# SH2_-_CONNECTORS.net
KiCad netlist of a schematic drawn in Altium Designer
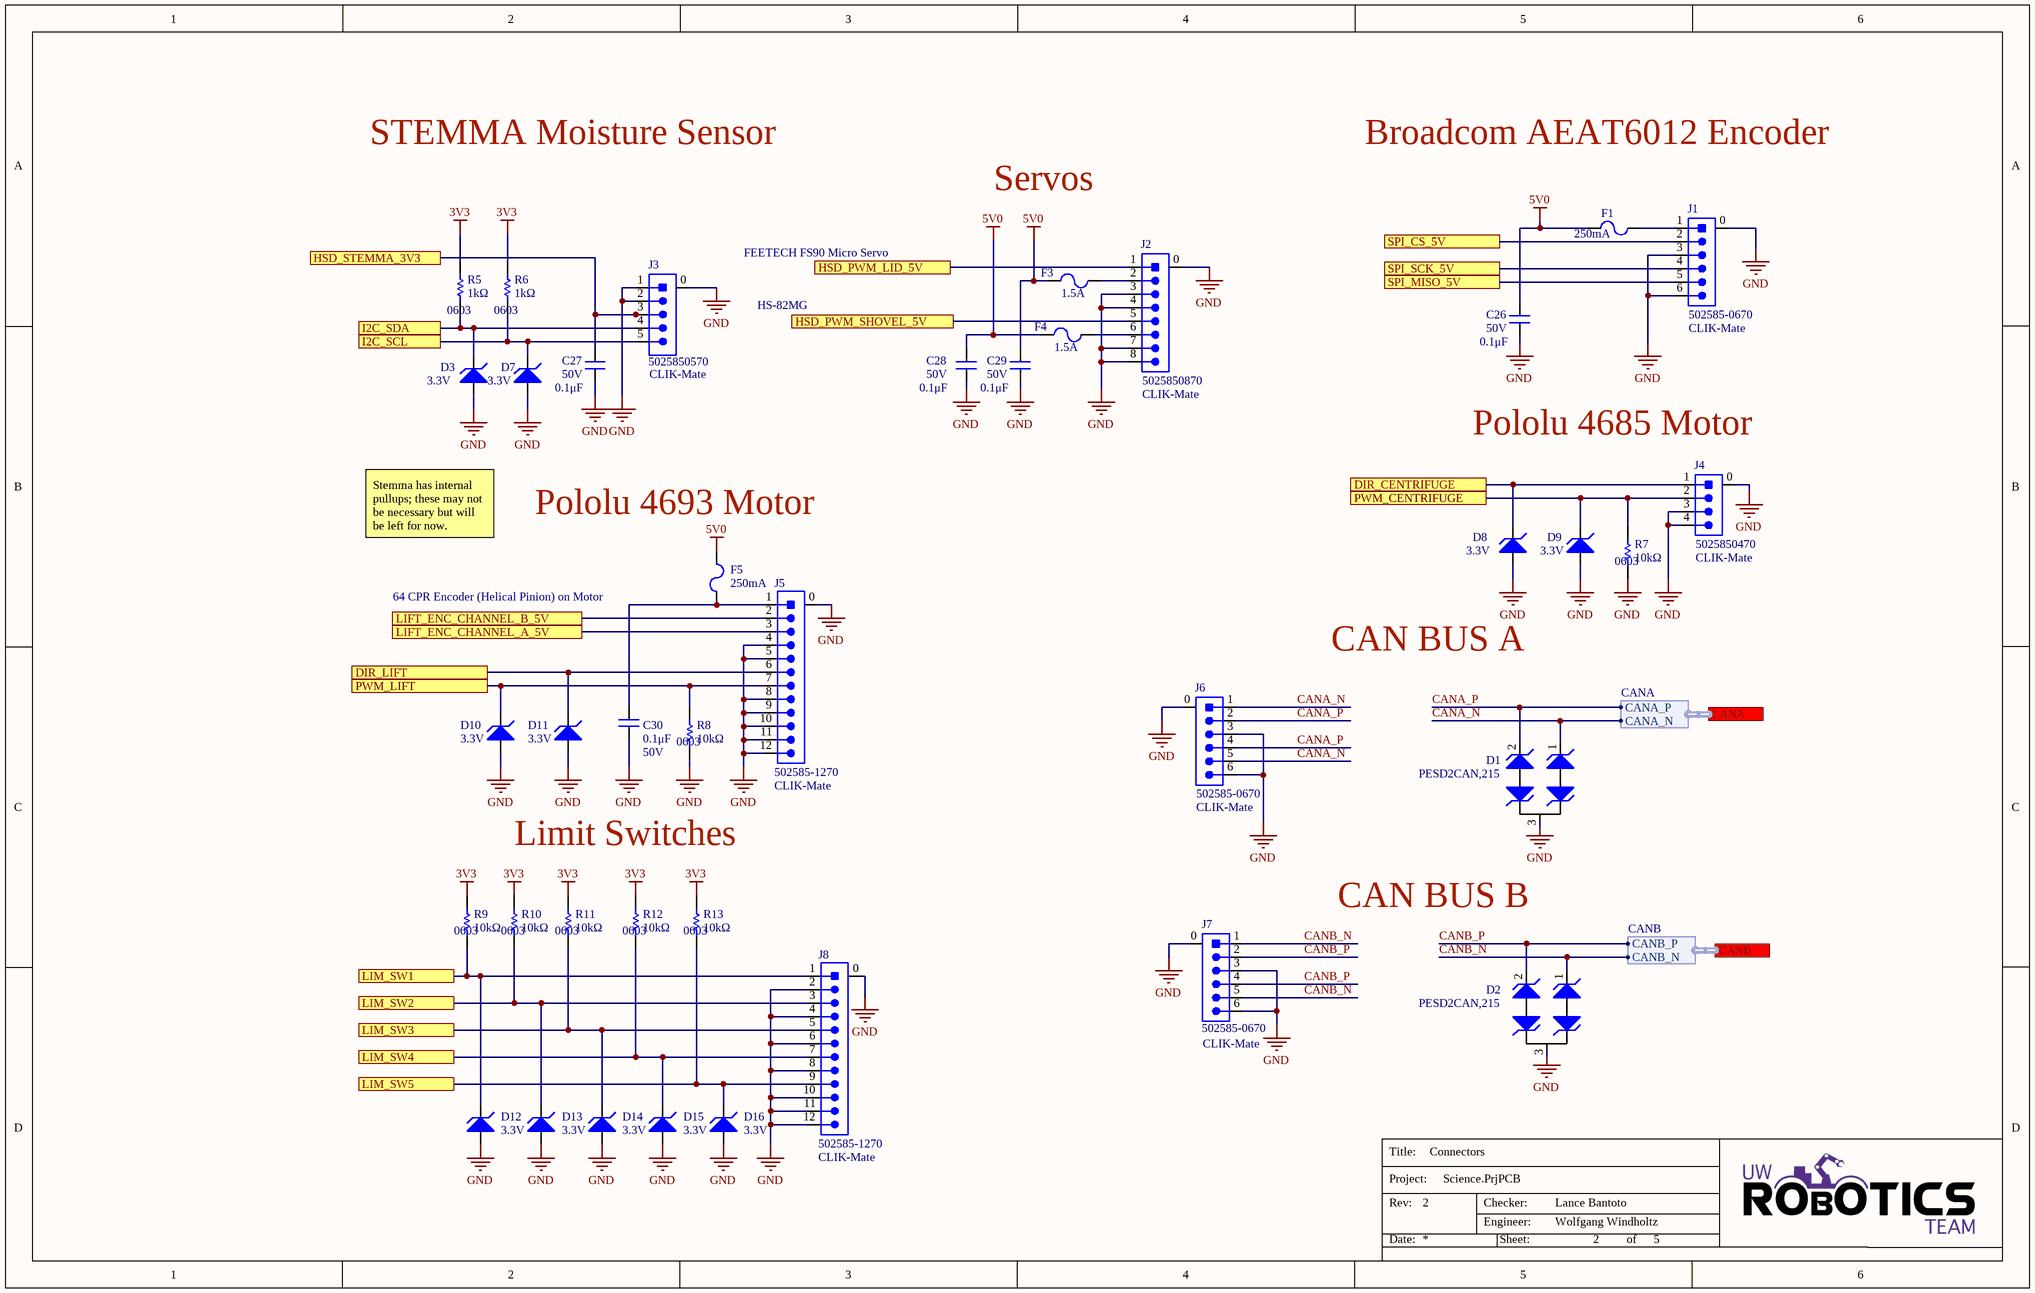
[diagram p0: SH2 - CONNECTORS.SchDoc]

(export (version "E")
  (design (tool "Eeschema 10.0.6"))
  (components
    (comp (ref "C26")
      (value "0.1μF")
      (footprint "CAP0603")
      (description "CAP CER 0.1UF 50V X7R 0603")
      (fields (field (name "VOLTAGE RATING") "50V") (field (name "Comment") "CAP_0.1uF_50V_0603"))
      (libsource (lib "UWRT_Schematic_Library_2020") (part "CAP_0.1uF_50V_0603"))
    )
    (comp (ref "C27")
      (value "0.1μF")
      (footprint "CAP0603")
      (description "CAP CER 0.1UF 50V X7R 0603")
      (fields (field (name "VOLTAGE RATING") "50V") (field (name "Comment") "CAP_0.1uF_50V_0603"))
      (libsource (lib "UWRT_Schematic_Library_2020") (part "CAP_0.1uF_50V_0603"))
    )
    (comp (ref "C28")
      (value "0.1μF")
      (footprint "CAP0603")
      (description "CAP CER 0.1UF 50V X7R 0603")
      (fields (field (name "VOLTAGE RATING") "50V") (field (name "Comment") "CAP_0.1uF_50V_0603"))
      (libsource (lib "UWRT_Schematic_Library_2020") (part "CAP_0.1uF_50V_0603"))
    )
    (comp (ref "C29")
      (value "0.1μF")
      (footprint "CAP0603")
      (description "CAP CER 0.1UF 50V X7R 0603")
      (fields (field (name "VOLTAGE RATING") "50V") (field (name "Comment") "CAP_0.1uF_50V_0603"))
      (libsource (lib "UWRT_Schematic_Library_2020") (part "CAP_0.1uF_50V_0603"))
    )
    (comp (ref "C30")
      (value "0.1μF")
      (footprint "CAP0603")
      (description "CAP CER 0.1UF 50V X7R 0603")
      (fields (field (name "VOLTAGE RATING") "50V") (field (name "Comment") "CAP_0.1uF_50V_0603"))
      (libsource (lib "UWRT_Schematic_Library_2020") (part "CAP_0.1uF_50V_0603"))
    )
    (comp (ref "D1")
      (value "TVS_DIODE_CAN")
      (footprint "TVS_DIODE_CAN")
      (description "TVS DIODE 24V 41V SOT323-3")
      (fields (field (name "MANUFACTURER PART NUMBER 1") "PESD2CAN,215"))
      (libsource (lib "UWRT_Schematic_Library_2020") (part "TVS_DIODE_CAN"))
    )
    (comp (ref "D2")
      (value "TVS_DIODE_CAN")
      (footprint "TVS_DIODE_CAN")
      (description "TVS DIODE 24V 41V SOT323-3")
      (fields (field (name "MANUFACTURER PART NUMBER 1") "PESD2CAN,215"))
      (libsource (lib "UWRT_Schematic_Library_2020") (part "TVS_DIODE_CAN"))
    )
    (comp (ref "D3")
      (value "ESD5Z3.3T1G")
      (footprint "SOD523_UNI")
      (description "TVS DIODE 3.3V 14.1V SOD523")
      (fields (field (name "REVERSE STANDOFF VOLTAGE") "3.3V"))
      (libsource (lib "UWRT_Schematic_Library_2020") (part "ESD5Z3.3T1G"))
    )
    (comp (ref "D7")
      (value "ESD5Z3.3T1G")
      (footprint "SOD523_UNI")
      (description "TVS DIODE 3.3V 14.1V SOD523")
      (fields (field (name "REVERSE STANDOFF VOLTAGE") "3.3V"))
      (libsource (lib "UWRT_Schematic_Library_2020") (part "ESD5Z3.3T1G"))
    )
    (comp (ref "D8")
      (value "ESD5Z3.3T1G")
      (footprint "SOD523_UNI")
      (description "TVS DIODE 3.3V 14.1V SOD523")
      (fields (field (name "REVERSE STANDOFF VOLTAGE") "3.3V"))
      (libsource (lib "UWRT_Schematic_Library_2020") (part "ESD5Z3.3T1G"))
    )
    (comp (ref "D9")
      (value "ESD5Z3.3T1G")
      (footprint "SOD523_UNI")
      (description "TVS DIODE 3.3V 14.1V SOD523")
      (fields (field (name "REVERSE STANDOFF VOLTAGE") "3.3V"))
      (libsource (lib "UWRT_Schematic_Library_2020") (part "ESD5Z3.3T1G"))
    )
    (comp (ref "D10")
      (value "ESD5Z3.3T1G")
      (footprint "SOD523_UNI")
      (description "TVS DIODE 3.3V 14.1V SOD523")
      (fields (field (name "REVERSE STANDOFF VOLTAGE") "3.3V"))
      (libsource (lib "UWRT_Schematic_Library_2020") (part "ESD5Z3.3T1G"))
    )
    (comp (ref "D11")
      (value "ESD5Z3.3T1G")
      (footprint "SOD523_UNI")
      (description "TVS DIODE 3.3V 14.1V SOD523")
      (fields (field (name "REVERSE STANDOFF VOLTAGE") "3.3V"))
      (libsource (lib "UWRT_Schematic_Library_2020") (part "ESD5Z3.3T1G"))
    )
    (comp (ref "D12")
      (value "ESD5Z3.3T1G")
      (footprint "SOD523_UNI")
      (description "TVS DIODE 3.3V 14.1V SOD523")
      (fields (field (name "REVERSE STANDOFF VOLTAGE") "3.3V"))
      (libsource (lib "UWRT_Schematic_Library_2020") (part "ESD5Z3.3T1G"))
    )
    (comp (ref "D13")
      (value "ESD5Z3.3T1G")
      (footprint "SOD523_UNI")
      (description "TVS DIODE 3.3V 14.1V SOD523")
      (fields (field (name "REVERSE STANDOFF VOLTAGE") "3.3V"))
      (libsource (lib "UWRT_Schematic_Library_2020") (part "ESD5Z3.3T1G"))
    )
    (comp (ref "D14")
      (value "ESD5Z3.3T1G")
      (footprint "SOD523_UNI")
      (description "TVS DIODE 3.3V 14.1V SOD523")
      (fields (field (name "REVERSE STANDOFF VOLTAGE") "3.3V"))
      (libsource (lib "UWRT_Schematic_Library_2020") (part "ESD5Z3.3T1G"))
    )
    (comp (ref "D15")
      (value "ESD5Z3.3T1G")
      (footprint "SOD523_UNI")
      (description "TVS DIODE 3.3V 14.1V SOD523")
      (fields (field (name "REVERSE STANDOFF VOLTAGE") "3.3V"))
      (libsource (lib "UWRT_Schematic_Library_2020") (part "ESD5Z3.3T1G"))
    )
    (comp (ref "D16")
      (value "ESD5Z3.3T1G")
      (footprint "SOD523_UNI")
      (description "TVS DIODE 3.3V 14.1V SOD523")
      (fields (field (name "REVERSE STANDOFF VOLTAGE") "3.3V"))
      (libsource (lib "UWRT_Schematic_Library_2020") (part "ESD5Z3.3T1G"))
    )
    (comp (ref "F1")
      (value "FUSE_250mA_1206")
      (footprint "FUSE_1206")
      (description "FUSE BOARD MNT 250MA 125VAC/VDC")
      (fields (field (name "CURRENT RATING") "250mA"))
      (libsource (lib "UWRT_Schematic_Library_2020") (part "FUSE_250mA_1206"))
    )
    (comp (ref "F3")
      (value "FUSE_1.5A_1206")
      (footprint "FUSE_1206")
      (description "FUSE SMD 1.5A 63V")
      (fields (field (name "CURRENT RATING") "1.5A"))
      (libsource (lib "UWRT_Schematic_Library_2020") (part "FUSE_1.5A_1206"))
    )
    (comp (ref "F4")
      (value "FUSE_1.5A_1206")
      (footprint "FUSE_1206")
      (description "FUSE SMD 1.5A 63V")
      (fields (field (name "CURRENT RATING") "1.5A"))
      (libsource (lib "UWRT_Schematic_Library_2020") (part "FUSE_1.5A_1206"))
    )
    (comp (ref "F5")
      (value "FUSE_250mA_1206")
      (footprint "FUSE_1206")
      (description "FUSE BOARD MNT 250MA 125VAC/VDC")
      (fields (field (name "CURRENT RATING") "250mA"))
      (libsource (lib "UWRT_Schematic_Library_2020") (part "FUSE_250mA_1206"))
    )
    (comp (ref "J1")
      (value "CON_6M_SM_RA_1.5mm")
      (footprint "MOLEX-5025850670")
      (description "CONN HEADER SMD RIGHT ANGLE 1.5 MM PITCH")
      (fields
        (field (name "MANUFACTOR NUMBER") "502585-0670")
        (field (name "MANUFACTURER") "Molex")
        (field (name "FAMILY") "CLIK-Mate")
      )
      (libsource (lib "UWRT_Schematic_Library_2020") (part "CON_6M_SM_RA_1.5mm"))
    )
    (comp (ref "J2")
      (value "CON_8M_SM_RA")
      (footprint "MOLEX-5025850870")
      (description "CONN HEADER SMD RIGHT ANGLE 1.5 MM PITCH")
      (fields
        (field (name "MANUFACTURER") "Molex")
        (field (name "MANUFACTURER PART NUMBER") "5025850870")
        (field (name "FAMILY") "CLIK-Mate")
      )
      (libsource (lib "UWRT_Schematic_Library_2020") (part "CON_8M_SM_RA"))
    )
    (comp (ref "J3")
      (value "CON_5M_SM_RA")
      (footprint "MOLEX-5025850570")
      (description "CONN HEADER SMD RIGHT ANGLE 1.5MM PITCH")
      (fields (field (name "MANUFACTURER PART NUMBER 1") "5025850570") (field (name "FAMILY") "CLIK-Mate"))
      (libsource (lib "UWRT_Schematic_Library_2020") (part "CON_5M_SM_RA"))
    )
    (comp (ref "J4")
      (value "CON_4M_SM_RA")
      (footprint "MOLEX-5025850470")
      (description "CONN HEADER SMD RIGHT ANGLE 1.5 MM PITCH")
      (fields
        (field (name "MANUFACTOR NUMBER") "5025850470")
        (field (name "MANUFACTURER") "Molex")
        (field (name "FAMILY") "CLIK-Mate")
      )
      (libsource (lib "UWRT_Schematic_Library_2020") (part "CON_4M_SM_RA"))
    )
    (comp (ref "J5")
      (value "CON_12M_SM_RA")
      (footprint "MOLEX-5025851270")
      (description "CONN HEADER SMD RIGHT ANGLE 1.5MM PITCH")
      (fields (field (name "FAMILY") "CLIK-Mate") (field (name "MANUFACTURER PART NUMBER 1") "502585-1270"))
      (libsource (lib "UWRT_Schematic_Library_2020") (part "CON_12M_SM_RA"))
    )
    (comp (ref "J6")
      (value "CON_6M_SM_RA_1.5mm")
      (footprint "MOLEX-5025850670")
      (description "CONN HEADER SMD RIGHT ANGLE 1.5 MM PITCH")
      (fields
        (field (name "MANUFACTOR NUMBER") "502585-0670")
        (field (name "MANUFACTURER") "Molex")
        (field (name "FAMILY") "CLIK-Mate")
      )
      (libsource (lib "") (part "CON_6M_SM_RA_1.5mm_1"))
    )
    (comp (ref "J7")
      (value "CON_6M_SM_RA_1.5mm")
      (footprint "MOLEX-5025850670")
      (description "CONN HEADER SMD RIGHT ANGLE 1.5 MM PITCH")
      (fields
        (field (name "MANUFACTOR NUMBER") "502585-0670")
        (field (name "MANUFACTURER") "Molex")
        (field (name "FAMILY") "CLIK-Mate")
      )
      (libsource (lib "") (part "CON_6M_SM_RA_1.5mm_1"))
    )
    (comp (ref "J8")
      (value "CON_12M_SM_RA")
      (footprint "MOLEX-5025851270")
      (description "CONN HEADER SMD RIGHT ANGLE 1.5MM PITCH")
      (fields (field (name "FAMILY") "CLIK-Mate") (field (name "MANUFACTURER PART NUMBER 1") "502585-1270"))
      (libsource (lib "UWRT_Schematic_Library_2020") (part "CON_12M_SM_RA"))
    )
    (comp (ref "R5")
      (value "1kΩ")
      (footprint "RESC0603")
      (description "RES 1K OHM 5% 1/10W 0603")
      (fields
        (field (name "TOLERANCE") "5%")
        (field (name "PACKAGE/FOOTPRINT") "0603")
        (field (name "Comment") "RES_1kΩ_0603_5%")
      )
      (libsource (lib "UWRT_Schematic_Library_2020") (part "RES_1kΩ_0603_5%"))
    )
    (comp (ref "R6")
      (value "1kΩ")
      (footprint "RESC0603")
      (description "RES 1K OHM 5% 1/10W 0603")
      (fields
        (field (name "TOLERANCE") "5%")
        (field (name "PACKAGE/FOOTPRINT") "0603")
        (field (name "Comment") "RES_1kΩ_0603_5%")
      )
      (libsource (lib "UWRT_Schematic_Library_2020") (part "RES_1kΩ_0603_5%"))
    )
    (comp (ref "R7")
      (value "10kΩ")
      (footprint "RESC0603")
      (description "RES 10K OHM 5% 1/10W 0603")
      (fields
        (field (name "TOLERANCE") "5%")
        (field (name "PACKAGE/FOOTPRINT") "0603")
        (field (name "Comment") "RES_10kΩ_0603_5%")
      )
      (libsource (lib "UWRT_Schematic_Library_2020") (part "RES_10kΩ_0603_5%"))
    )
    (comp (ref "R8")
      (value "10kΩ")
      (footprint "RESC0603")
      (description "RES 10K OHM 5% 1/10W 0603")
      (fields
        (field (name "TOLERANCE") "5%")
        (field (name "PACKAGE/FOOTPRINT") "0603")
        (field (name "Comment") "RES_10kΩ_0603_5%")
      )
      (libsource (lib "UWRT_Schematic_Library_2020") (part "RES_10kΩ_0603_5%"))
    )
    (comp (ref "R9")
      (value "10kΩ")
      (footprint "RESC0603")
      (description "RES 10K OHM 5% 1/10W 0603")
      (fields
        (field (name "TOLERANCE") "5%")
        (field (name "PACKAGE/FOOTPRINT") "0603")
        (field (name "Comment") "RES_10kΩ_0603_5%")
      )
      (libsource (lib "UWRT_Schematic_Library_2020") (part "RES_10kΩ_0603_5%"))
    )
    (comp (ref "R10")
      (value "10kΩ")
      (footprint "RESC0603")
      (description "RES 10K OHM 5% 1/10W 0603")
      (fields
        (field (name "TOLERANCE") "5%")
        (field (name "PACKAGE/FOOTPRINT") "0603")
        (field (name "Comment") "RES_10kΩ_0603_5%")
      )
      (libsource (lib "UWRT_Schematic_Library_2020") (part "RES_10kΩ_0603_5%"))
    )
    (comp (ref "R11")
      (value "10kΩ")
      (footprint "RESC0603")
      (description "RES 10K OHM 5% 1/10W 0603")
      (fields
        (field (name "TOLERANCE") "5%")
        (field (name "PACKAGE/FOOTPRINT") "0603")
        (field (name "Comment") "RES_10kΩ_0603_5%")
      )
      (libsource (lib "UWRT_Schematic_Library_2020") (part "RES_10kΩ_0603_5%"))
    )
    (comp (ref "R12")
      (value "10kΩ")
      (footprint "RESC0603")
      (description "RES 10K OHM 5% 1/10W 0603")
      (fields
        (field (name "TOLERANCE") "5%")
        (field (name "PACKAGE/FOOTPRINT") "0603")
        (field (name "Comment") "RES_10kΩ_0603_5%")
      )
      (libsource (lib "UWRT_Schematic_Library_2020") (part "RES_10kΩ_0603_5%"))
    )
    (comp (ref "R13")
      (value "10kΩ")
      (footprint "RESC0603")
      (description "RES 10K OHM 5% 1/10W 0603")
      (fields
        (field (name "TOLERANCE") "5%")
        (field (name "PACKAGE/FOOTPRINT") "0603")
        (field (name "Comment") "RES_10kΩ_0603_5%")
      )
      (libsource (lib "UWRT_Schematic_Library_2020") (part "RES_10kΩ_0603_5%"))
    )
  )
  (nets
    (net (code "3") (name "/CANA_N") (class "Default")
      (node (ref "D1") (pin "1") (pinfunction "1_1") (pintype "passive"))
      (node (ref "J6") (pin "1") (pinfunction "1_1") (pintype "passive"))
      (node (ref "J6") (pin "5") (pinfunction "5_5") (pintype "passive"))
    )
    (net (code "4") (name "/CANA_P") (class "Default")
      (node (ref "D1") (pin "2") (pinfunction "2_2") (pintype "passive"))
      (node (ref "J6") (pin "2") (pinfunction "2_2") (pintype "passive"))
      (node (ref "J6") (pin "4") (pinfunction "4_4") (pintype "passive"))
    )
    (net (code "5") (name "/CANB_N") (class "Default")
      (node (ref "D2") (pin "1") (pinfunction "1_1") (pintype "passive"))
      (node (ref "J7") (pin "1") (pinfunction "1_1") (pintype "passive"))
      (node (ref "J7") (pin "5") (pinfunction "5_5") (pintype "passive"))
    )
    (net (code "6") (name "/CANB_P") (class "Default")
      (node (ref "D2") (pin "2") (pinfunction "2_2") (pintype "passive"))
      (node (ref "J7") (pin "2") (pinfunction "2_2") (pintype "passive"))
      (node (ref "J7") (pin "4") (pinfunction "4_4") (pintype "passive"))
    )
    (net (code "7") (name "/DIR_CENTRIFUGE") (class "Default")
      (node (ref "D8") (pin "2") (pinfunction "Cathode_2") (pintype "passive"))
      (node (ref "J4") (pin "1") (pinfunction "1_1") (pintype "passive"))
    )
    (net (code "8") (name "/DIR_LIFT") (class "Default")
      (node (ref "D11") (pin "2") (pinfunction "Cathode_2") (pintype "passive"))
      (node (ref "J5") (pin "6") (pinfunction "6_6") (pintype "passive"))
    )
    (net (code "9") (name "/HSD_PWM_LID_5V") (class "Default")
      (node (ref "J2") (pin "1") (pinfunction "1_1") (pintype "passive"))
    )
    (net (code "10") (name "/HSD_PWM_SHOVEL_5V") (class "Default")
      (node (ref "J2") (pin "5") (pinfunction "5_5") (pintype "passive"))
    )
    (net (code "11") (name "/HSD_STEMMA_3V3") (class "Default")
      (node (ref "C27") (pin "2") (pinfunction "2_2") (pintype "passive"))
      (node (ref "J3") (pin "3") (pinfunction "3_3") (pintype "passive"))
    )
    (net (code "12") (name "/I2C_SCL") (class "Default")
      (node (ref "D7") (pin "2") (pinfunction "Cathode_2") (pintype "passive"))
      (node (ref "J3") (pin "5") (pinfunction "5_5") (pintype "passive"))
      (node (ref "R6") (pin "1") (pinfunction "1_1") (pintype "passive"))
    )
    (net (code "13") (name "/I2C_SDA") (class "Default")
      (node (ref "D3") (pin "2") (pinfunction "Cathode_2") (pintype "passive"))
      (node (ref "J3") (pin "4") (pinfunction "4_4") (pintype "passive"))
      (node (ref "R5") (pin "1") (pinfunction "1_1") (pintype "passive"))
    )
    (net (code "14") (name "/LIFT_ENC_CHANNEL_A_5V") (class "Default")
      (node (ref "J5") (pin "3") (pinfunction "3_3") (pintype "passive"))
    )
    (net (code "15") (name "/LIFT_ENC_CHANNEL_B_5V") (class "Default")
      (node (ref "J5") (pin "2") (pinfunction "2_2") (pintype "passive"))
    )
    (net (code "16") (name "/LIM_SW1") (class "Default")
      (node (ref "D12") (pin "2") (pinfunction "Cathode_2") (pintype "passive"))
      (node (ref "J8") (pin "1") (pinfunction "1_1") (pintype "passive"))
      (node (ref "R9") (pin "1") (pinfunction "1_1") (pintype "passive"))
    )
    (net (code "17") (name "/LIM_SW2") (class "Default")
      (node (ref "D13") (pin "2") (pinfunction "Cathode_2") (pintype "passive"))
      (node (ref "J8") (pin "3") (pinfunction "3_3") (pintype "passive"))
      (node (ref "R10") (pin "1") (pinfunction "1_1") (pintype "passive"))
    )
    (net (code "18") (name "/LIM_SW3") (class "Default")
      (node (ref "D14") (pin "2") (pinfunction "Cathode_2") (pintype "passive"))
      (node (ref "J8") (pin "5") (pinfunction "5_5") (pintype "passive"))
      (node (ref "R11") (pin "1") (pinfunction "1_1") (pintype "passive"))
    )
    (net (code "19") (name "/LIM_SW4") (class "Default")
      (node (ref "D15") (pin "2") (pinfunction "Cathode_2") (pintype "passive"))
      (node (ref "J8") (pin "7") (pinfunction "6_7") (pintype "passive"))
      (node (ref "R12") (pin "1") (pinfunction "1_1") (pintype "passive"))
    )
    (net (code "20") (name "/LIM_SW5") (class "Default")
      (node (ref "D16") (pin "2") (pinfunction "Cathode_2") (pintype "passive"))
      (node (ref "J8") (pin "9") (pinfunction "9_9") (pintype "passive"))
      (node (ref "R13") (pin "1") (pinfunction "1_1") (pintype "passive"))
    )
    (net (code "21") (name "/PWM_CENTRIFUGE") (class "Default")
      (node (ref "D9") (pin "2") (pinfunction "Cathode_2") (pintype "passive"))
      (node (ref "J4") (pin "2") (pinfunction "2_2") (pintype "passive"))
      (node (ref "R7") (pin "2") (pinfunction "2_2") (pintype "passive"))
    )
    (net (code "22") (name "/PWM_LIFT") (class "Default")
      (node (ref "D10") (pin "2") (pinfunction "Cathode_2") (pintype "passive"))
      (node (ref "J5") (pin "7") (pinfunction "6_7") (pintype "passive"))
      (node (ref "R8") (pin "2") (pinfunction "2_2") (pintype "passive"))
    )
    (net (code "23") (name "/SPI_CS_5V") (class "Default")
      (node (ref "J1") (pin "2") (pinfunction "2_2") (pintype "passive"))
    )
    (net (code "24") (name "/SPI_MISO_5V") (class "Default")
      (node (ref "J1") (pin "5") (pinfunction "5_5") (pintype "passive"))
    )
    (net (code "25") (name "/SPI_SCK_5V") (class "Default")
      (node (ref "J1") (pin "4") (pinfunction "4_4") (pintype "passive"))
    )
    (net (code "28") (name "3V3") (class "Default")
      (node (ref "R10") (pin "2") (pinfunction "2_2") (pintype "passive"))
      (node (ref "R11") (pin "2") (pinfunction "2_2") (pintype "passive"))
      (node (ref "R12") (pin "2") (pinfunction "2_2") (pintype "passive"))
      (node (ref "R13") (pin "2") (pinfunction "2_2") (pintype "passive"))
      (node (ref "R5") (pin "2") (pinfunction "2_2") (pintype "passive"))
      (node (ref "R6") (pin "2") (pinfunction "2_2") (pintype "passive"))
      (node (ref "R9") (pin "2") (pinfunction "2_2") (pintype "passive"))
    )
    (net (code "29") (name "5V0") (class "Default")
      (node (ref "C26") (pin "2") (pinfunction "2_2") (pintype "passive"))
      (node (ref "C28") (pin "2") (pinfunction "2_2") (pintype "passive"))
      (node (ref "C29") (pin "2") (pinfunction "2_2") (pintype "passive"))
      (node (ref "F1") (pin "2") (pinfunction "2_2") (pintype "passive"))
      (node (ref "F3") (pin "1") (pinfunction "1_1") (pintype "passive"))
      (node (ref "F4") (pin "1") (pinfunction "1_1") (pintype "passive"))
      (node (ref "F5") (pin "2") (pinfunction "2_2") (pintype "passive"))
    )
    (net (code "30") (name "GND") (class "Default")
      (node (ref "C26") (pin "1") (pinfunction "1_1") (pintype "passive"))
      (node (ref "C27") (pin "1") (pinfunction "1_1") (pintype "passive"))
      (node (ref "C28") (pin "1") (pinfunction "1_1") (pintype "passive"))
      (node (ref "C29") (pin "1") (pinfunction "1_1") (pintype "passive"))
      (node (ref "C30") (pin "1") (pinfunction "1_1") (pintype "passive"))
      (node (ref "D1") (pin "3") (pinfunction "3_3") (pintype "passive"))
      (node (ref "D10") (pin "1") (pinfunction "Anode_1") (pintype "passive"))
      (node (ref "D11") (pin "1") (pinfunction "Anode_1") (pintype "passive"))
      (node (ref "D12") (pin "1") (pinfunction "Anode_1") (pintype "passive"))
      (node (ref "D13") (pin "1") (pinfunction "Anode_1") (pintype "passive"))
      (node (ref "D14") (pin "1") (pinfunction "Anode_1") (pintype "passive"))
      (node (ref "D15") (pin "1") (pinfunction "Anode_1") (pintype "passive"))
      (node (ref "D16") (pin "1") (pinfunction "Anode_1") (pintype "passive"))
      (node (ref "D2") (pin "3") (pinfunction "3_3") (pintype "passive"))
      (node (ref "D3") (pin "1") (pinfunction "Anode_1") (pintype "passive"))
      (node (ref "D7") (pin "1") (pinfunction "Anode_1") (pintype "passive"))
      (node (ref "D8") (pin "1") (pinfunction "Anode_1") (pintype "passive"))
      (node (ref "D9") (pin "1") (pinfunction "Anode_1") (pintype "passive"))
      (node (ref "J1") (pin "0") (pinfunction "0_0") (pintype "passive"))
      (node (ref "J1") (pin "3") (pinfunction "3_3") (pintype "passive"))
      (node (ref "J1") (pin "6") (pinfunction "6_6") (pintype "passive"))
      (node (ref "J2") (pin "0") (pinfunction "0_0") (pintype "passive"))
      (node (ref "J2") (pin "3") (pinfunction "3_3") (pintype "passive"))
      (node (ref "J2") (pin "4") (pinfunction "4_4") (pintype "passive"))
      (node (ref "J2") (pin "7") (pinfunction "6_7") (pintype "passive"))
      (node (ref "J2") (pin "8") (pinfunction "6_8") (pintype "passive"))
      (node (ref "J3") (pin "0") (pinfunction "0_0") (pintype "passive"))
      (node (ref "J3") (pin "1") (pinfunction "1_1") (pintype "passive"))
      (node (ref "J3") (pin "2") (pinfunction "2_2") (pintype "passive"))
      (node (ref "J4") (pin "0") (pinfunction "0_0") (pintype "passive"))
      (node (ref "J4") (pin "3") (pinfunction "3_3") (pintype "passive"))
      (node (ref "J4") (pin "4") (pinfunction "4_4") (pintype "passive"))
      (node (ref "J5") (pin "0") (pinfunction "0_0") (pintype "passive"))
      (node (ref "J5") (pin "10") (pinfunction "10_10") (pintype "passive"))
      (node (ref "J5") (pin "11") (pinfunction "11_11") (pintype "passive"))
      (node (ref "J5") (pin "12") (pinfunction "12_12") (pintype "passive"))
      (node (ref "J5") (pin "4") (pinfunction "4_4") (pintype "passive"))
      (node (ref "J5") (pin "5") (pinfunction "5_5") (pintype "passive"))
      (node (ref "J5") (pin "8") (pinfunction "6_8") (pintype "passive"))
      (node (ref "J5") (pin "9") (pinfunction "9_9") (pintype "passive"))
      (node (ref "J6") (pin "0") (pinfunction "0_0") (pintype "passive"))
      (node (ref "J6") (pin "3") (pinfunction "3_3") (pintype "passive"))
      (node (ref "J6") (pin "6") (pinfunction "6_6") (pintype "passive"))
      (node (ref "J7") (pin "0") (pinfunction "0_0") (pintype "passive"))
      (node (ref "J7") (pin "3") (pinfunction "3_3") (pintype "passive"))
      (node (ref "J7") (pin "6") (pinfunction "6_6") (pintype "passive"))
      (node (ref "J8") (pin "0") (pinfunction "0_0") (pintype "passive"))
      (node (ref "J8") (pin "10") (pinfunction "10_10") (pintype "passive"))
      (node (ref "J8") (pin "11") (pinfunction "11_11") (pintype "passive"))
      (node (ref "J8") (pin "12") (pinfunction "12_12") (pintype "passive"))
      (node (ref "J8") (pin "2") (pinfunction "2_2") (pintype "passive"))
      (node (ref "J8") (pin "4") (pinfunction "4_4") (pintype "passive"))
      (node (ref "J8") (pin "6") (pinfunction "6_6") (pintype "passive"))
      (node (ref "J8") (pin "8") (pinfunction "6_8") (pintype "passive"))
      (node (ref "R7") (pin "1") (pinfunction "1_1") (pintype "passive"))
      (node (ref "R8") (pin "1") (pinfunction "1_1") (pintype "passive"))
    )
    (net (code "31") (name "Net-(C30-Pad2)") (class "Default")
      (node (ref "C30") (pin "2") (pinfunction "2_2") (pintype "passive"))
      (node (ref "F5") (pin "1") (pinfunction "1_1") (pintype "passive"))
      (node (ref "J5") (pin "1") (pinfunction "1_1") (pintype "passive"))
    )
    (net (code "32") (name "Net-(F1-Pad1)") (class "Default")
      (node (ref "F1") (pin "1") (pinfunction "1_1") (pintype "passive"))
      (node (ref "J1") (pin "1") (pinfunction "1_1") (pintype "passive"))
    )
    (net (code "33") (name "Net-(F3-Pad2)") (class "Default")
      (node (ref "F3") (pin "2") (pinfunction "2_2") (pintype "passive"))
      (node (ref "J2") (pin "2") (pinfunction "2_2") (pintype "passive"))
    )
    (net (code "34") (name "Net-(F4-Pad2)") (class "Default")
      (node (ref "F4") (pin "2") (pinfunction "2_2") (pintype "passive"))
      (node (ref "J2") (pin "6") (pinfunction "6_6") (pintype "passive"))
    )
  )
)
